# LED.net
KiCad netlist of a schematic drawn in Altium Designer
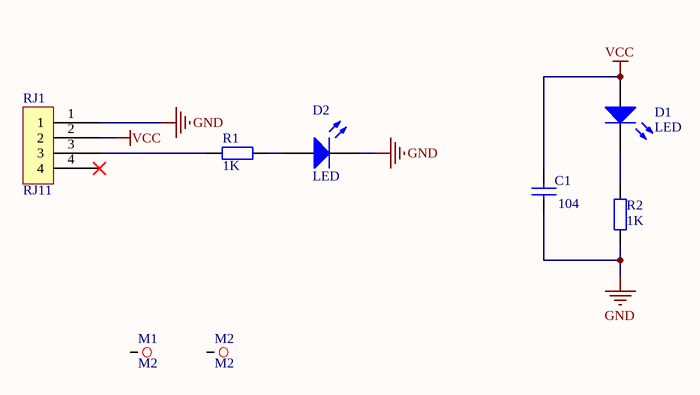
[diagram p0: LED.SchDoc]

(export (version "E")
  (design (tool "Eeschema 10.0.6"))
  (components
    (comp (ref "C1")
      (value "104")
      (footprint "0603_C")
      (description "Capacitor")
      (fields (field (name "Comment") "Cap") (field (name "PUBLISHER") "Altium Limited"))
      (libsource (lib "Miscellaneous Devices") (part "Cap"))
    )
    (comp (ref "D1")
      (value "LED")
      (footprint "0805")
      (description "Typical RED GaAs LED")
      (fields (field (name "PUBLISHER") "Altium Limited"))
      (libsource (lib "Miscellaneous Devices") (part "LED1"))
    )
    (comp (ref "D2")
      (value "LED")
      (footprint "LED-10MM")
      (description "Typical RED GaAs LED")
      (fields (field (name "PUBLISHER") "Altium Limited"))
      (libsource (lib "Miscellaneous Devices") (part "LED1"))
    )
    (comp (ref "M1") (value "M2") (footprint "M2") (libsource (lib "QQW-1.SCHLIB") (part "M3")))
    (comp (ref "M2") (value "M2") (footprint "M2") (libsource (lib "QQW-1.SCHLIB") (part "M3")))
    (comp (ref "R1")
      (value "1K")
      (footprint "0603_R")
      (description "Resistor")
      (fields (field (name "Comment") "Res2") (field (name "PUBLISHER") "Altium Limited"))
      (libsource (lib "Miscellaneous Devices") (part "Res2"))
    )
    (comp (ref "R2")
      (value "1K")
      (footprint "0603_R")
      (description "Resistor")
      (fields (field (name "Comment") "Res2") (field (name "PUBLISHER") "Altium Limited"))
      (libsource (lib "") (part "Res2_1"))
    )
    (comp (ref "RJ1") (value "RJ11") (footprint "RJ11") (libsource (lib "少儿智能车") (part "RJ11")))
  )
  (nets
    (net (code "1") (name "GND") (class "Default")
      (node (ref "C1") (pin "1") (pinfunction "1_1") (pintype "passive"))
      (node (ref "D2") (pin "2") (pinfunction "K_2") (pintype "passive"))
      (node (ref "R2") (pin "1") (pinfunction "1_1") (pintype "passive"))
      (node (ref "RJ1") (pin "1") (pinfunction "1_1") (pintype "passive"))
    )
    (net (code "2") (name "Net-(D1-K)") (class "Default")
      (node (ref "D1") (pin "2") (pinfunction "K_2") (pintype "passive"))
      (node (ref "R2") (pin "2") (pinfunction "2_2") (pintype "passive"))
    )
    (net (code "3") (name "Net-(D2-A)") (class "Default")
      (node (ref "D2") (pin "1") (pinfunction "A_1") (pintype "passive"))
      (node (ref "R1") (pin "1") (pinfunction "1_1") (pintype "passive"))
    )
    (net (code "4") (name "Net-(R1-Pad2)") (class "Default")
      (node (ref "R1") (pin "2") (pinfunction "2_2") (pintype "passive"))
      (node (ref "RJ1") (pin "3") (pinfunction "3_3") (pintype "passive"))
    )
    (net (code "5") (name "VCC") (class "Default")
      (node (ref "C1") (pin "2") (pinfunction "2_2") (pintype "passive"))
      (node (ref "D1") (pin "1") (pinfunction "A_1") (pintype "passive"))
      (node (ref "RJ1") (pin "2") (pinfunction "2_2") (pintype "passive"))
    )
    (net (code "6") (name "unconnected-(M1-Pad0)") (class "Default")
      (node (ref "M1") (pin "0") (pinfunction "0_0") (pintype "passive"))
    )
    (net (code "7") (name "unconnected-(M2-Pad0)") (class "Default")
      (node (ref "M2") (pin "0") (pinfunction "0_0") (pintype "passive"))
    )
    (net (code "8") (name "unconnected-(RJ1-Pad4)") (class "Default")
      (node (ref "RJ1") (pin "4") (pinfunction "4_4") (pintype "passive+no_connect"))
    )
  )
)
